# AMS_MCU.net
KiCad netlist of a schematic drawn in Altium Designer
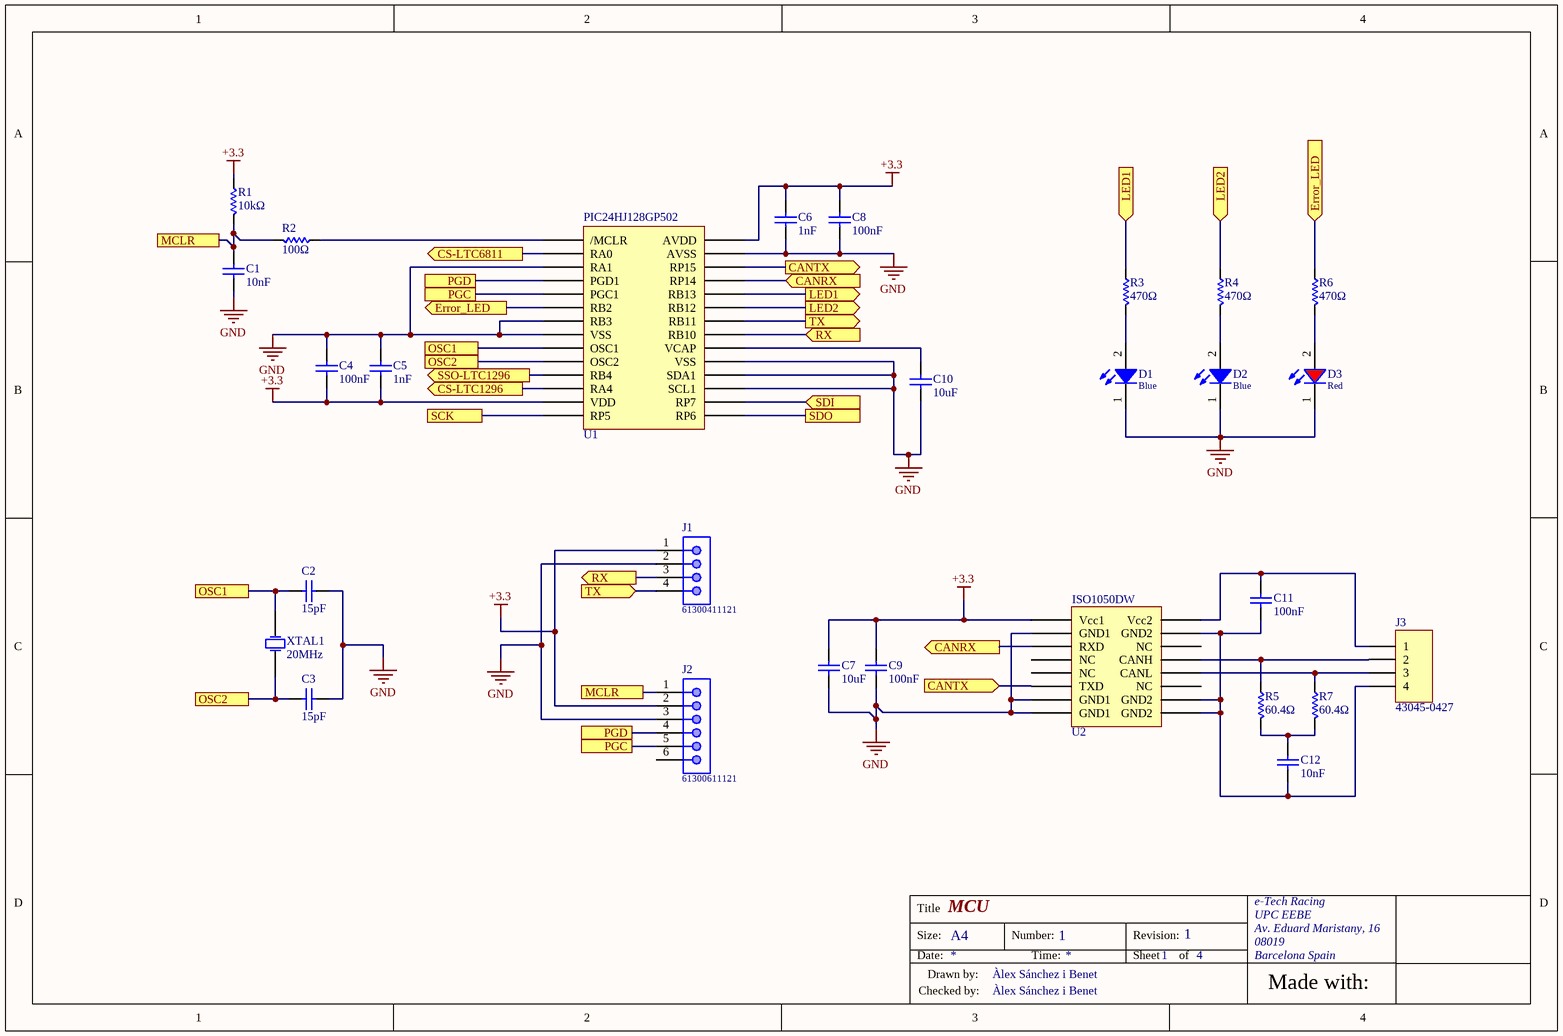
[diagram p0: AMS_MCU.SchDoc]

(export (version "E")
  (design (tool "Eeschema 10.0.6"))
  (components
    (comp (ref "C1")
      (value "10nF")
      (footprint "0805_2x1.25x0.8mm_Reflow Soldering")
      (description "WCAP-CSGP Ceramic Capacitors, 0805, X7R, 50V, 10nF")
      (fields (field (name "PART NUMBER") "885012207092") (field (name "PUBLISHER") "Wurth Elektronik"))
      (libsource (lib "Components_Library") (part "885012207092"))
    )
    (comp (ref "C2")
      (value "15pF")
      (footprint "0805_2x1.25x0.6mm_Reflow Soldering")
      (description "WCAP-CSGP Ceramic Capacitors, 0805, NP0, 50V, 15pF")
      (fields (field (name "PART NUMBER") "885012007052") (field (name "PUBLISHER") "Wurth Elektronik"))
      (libsource (lib "Components_Library") (part "885012007052"))
    )
    (comp (ref "C3")
      (value "15pF")
      (footprint "0805_2x1.25x0.6mm_Reflow Soldering")
      (description "WCAP-CSGP Ceramic Capacitors, 0805, NP0, 50V, 15pF")
      (fields (field (name "PART NUMBER") "885012007052") (field (name "PUBLISHER") "Wurth Elektronik"))
      (libsource (lib "Components_Library") (part "885012007052"))
    )
    (comp (ref "C4")
      (value "100nF")
      (footprint "0805_2x1.25x0.8mm_Reflow Soldering")
      (description "WCAP-CSGP Ceramic Capacitors, 0805, X7R, 50V, 100nF")
      (fields (field (name "PART NUMBER") "885012207098") (field (name "PUBLISHER") "Wurth Elektronik"))
      (libsource (lib "Components_Library") (part "885012207098"))
    )
    (comp (ref "C5")
      (value "1nF")
      (footprint "0805_2x1.25x0.8mm_Reflow Soldering")
      (description "WCAP-CSGP Ceramic Capacitors, 0805, NP0, 50V, 1nF")
      (fields (field (name "PART NUMBER") "885012007063") (field (name "PUBLISHER") "Wurth Elektronik"))
      (libsource (lib "Components_Library") (part "885012007063"))
    )
    (comp (ref "C6")
      (value "1nF")
      (footprint "0805_2x1.25x0.8mm_Reflow Soldering")
      (description "WCAP-CSGP Ceramic Capacitors, 0805, NP0, 50V, 1nF")
      (fields (field (name "PART NUMBER") "885012007063") (field (name "PUBLISHER") "Wurth Elektronik"))
      (libsource (lib "Components_Library") (part "885012007063"))
    )
    (comp (ref "C7")
      (value "10uF")
      (footprint "0805_2x1.25x1.25mm_Reflow Soldering")
      (description "WCAP-CSGP Ceramic Capacitors, 0805, X5R, 16V, 10uF")
      (fields (field (name "PART NUMBER") "885012107014") (field (name "PUBLISHER") "Wurth Elektronik"))
      (libsource (lib "Components_Library") (part "885012107014"))
    )
    (comp (ref "C8")
      (value "100nF")
      (footprint "0805_2x1.25x0.8mm_Reflow Soldering")
      (description "WCAP-CSGP Ceramic Capacitors, 0805, X7R, 50V, 100nF")
      (fields (field (name "PART NUMBER") "885012207098") (field (name "PUBLISHER") "Wurth Elektronik"))
      (libsource (lib "Components_Library") (part "885012207098"))
    )
    (comp (ref "C9")
      (value "100nF")
      (footprint "0805_2x1.25x0.8mm_Reflow Soldering")
      (description "WCAP-CSGP Ceramic Capacitors, 0805, X7R, 50V, 100nF")
      (fields (field (name "PART NUMBER") "885012207098") (field (name "PUBLISHER") "Wurth Elektronik"))
      (libsource (lib "Components_Library") (part "885012207098"))
    )
    (comp (ref "C10")
      (value "10uF")
      (footprint "0805_2x1.25x1.25mm_Reflow Soldering")
      (description "WCAP-CSGP Ceramic Capacitors, 0805, X5R, 16V, 10uF")
      (fields (field (name "PART NUMBER") "885012107014") (field (name "PUBLISHER") "Wurth Elektronik"))
      (libsource (lib "Components_Library") (part "885012107014"))
    )
    (comp (ref "C11")
      (value "100nF")
      (footprint "0805_2x1.25x0.8mm_Reflow Soldering")
      (description "WCAP-CSGP Ceramic Capacitors, 0805, X7R, 50V, 100nF")
      (fields (field (name "PART NUMBER") "885012207098") (field (name "PUBLISHER") "Wurth Elektronik"))
      (libsource (lib "Components_Library") (part "885012207098"))
    )
    (comp (ref "C12")
      (value "10nF")
      (footprint "0805_2x1.25x0.8mm_Reflow Soldering")
      (description "WCAP-CSGP Ceramic Capacitors, 0805, X7R, 50V, 10nF")
      (fields (field (name "PART NUMBER") "885012207092") (field (name "PUBLISHER") "Wurth Elektronik"))
      (libsource (lib "Components_Library") (part "885012207092"))
    )
    (comp (ref "D1")
      (value "Blue")
      (footprint "WL-SMCW_0805")
      (description "SMT Mono-color Chip LED Waterclear WL-SMCW, size 0805, Blue, 3.2 V, 140 deg, 145 mcd")
      (fields (field (name "PART NUMBER") "150080BS75000") (field (name "PUBLISHER") "Wurth Elektronik"))
      (libsource (lib "Components_Library") (part "150080BS75000"))
    )
    (comp (ref "D2")
      (value "Blue")
      (footprint "WL-SMCW_0805")
      (description "SMT Mono-color Chip LED Waterclear WL-SMCW, size 0805, Blue, 3.2 V, 140 deg, 145 mcd")
      (fields (field (name "PART NUMBER") "150080BS75000") (field (name "PUBLISHER") "Wurth Elektronik"))
      (libsource (lib "Components_Library") (part "150080BS75000"))
    )
    (comp (ref "D3")
      (value "Red")
      (footprint "WL-SMCW_0805")
      (description "SMT Mono-color Chip LED Waterclear WL-SMCW, size 0805, Red, 2 V, 140 deg, 150 mcd")
      (fields (field (name "PART NUMBER") "150080RS75000") (field (name "PUBLISHER") "Wurth Elektronik"))
      (libsource (lib "Components_Library") (part "150080RS75000"))
    )
    (comp (ref "J1")
      (value "61300411121")
      (footprint "61300411121")
      (description "THT Vertical Pin Header WR-PHD, Pitch 2.54 mm, Single Row, 4 pins")
      (fields (field (name "PUBLISHER") "Wurth Elektronik"))
      (libsource (lib "Components_Library") (part "61300411121"))
    )
    (comp (ref "J2")
      (value "61300611121")
      (footprint "61300611121")
      (description "THT Vertical Pin Header WR-PHD, Pitch 2.54 mm, Single Row, 6 pins")
      (fields (field (name "PUBLISHER") "Wurth Elektronik"))
      (libsource (lib "Components_Library") (part "61300611121"))
    )
    (comp (ref "J3")
      (value "43045-0427")
      (footprint "43045-0427")
      (description "Micro-Fit 3.0 Vertical Header, 3.00mm Pitch, Dual Row, 4 Circuits, Black")
      (fields (field (name "MANUFACTURER") "Molex"))
      (libsource (lib "Components_Library") (part "43045-0427"))
    )
    (comp (ref "R1")
      (value "10kΩ")
      (footprint "CR0805")
      (description "Chip Resistor 0805")
      (fields (field (name "MANUFACTURER") "Bourns"))
      (libsource (lib "Components_Library") (part "CR0805-JW-103ELF"))
    )
    (comp (ref "R2")
      (value "100Ω")
      (footprint "CR0805")
      (description "Chip Resistor 0805")
      (fields (field (name "MANUFACTURER") "Bourns"))
      (libsource (lib "Components_Library") (part "CR0805-FX-1000ELF"))
    )
    (comp (ref "R3")
      (value "470Ω")
      (footprint "CR0805")
      (description "Chip Resistor 0805")
      (fields (field (name "MANUFACTURER") "Bourns"))
      (libsource (lib "Components_Library") (part "CR0805-FX-4700GLF"))
    )
    (comp (ref "R4")
      (value "470Ω")
      (footprint "CR0805")
      (description "Chip Resistor 0805")
      (fields (field (name "MANUFACTURER") "Bourns"))
      (libsource (lib "Components_Library") (part "CR0805-FX-4700GLF"))
    )
    (comp (ref "R5")
      (value "60.4Ω")
      (footprint "CR0805")
      (description "Chip Resistor 0805")
      (fields (field (name "MANUFACTURER") "Panasonic"))
      (libsource (lib "Components_Library") (part "ERA6AEB60R4V"))
    )
    (comp (ref "R6")
      (value "470Ω")
      (footprint "CR0805")
      (description "Chip Resistor 0805")
      (fields (field (name "MANUFACTURER") "Bourns"))
      (libsource (lib "Components_Library") (part "CR0805-FX-4700GLF"))
    )
    (comp (ref "R7")
      (value "60.4Ω")
      (footprint "CR0805")
      (description "Chip Resistor 0805")
      (fields (field (name "MANUFACTURER") "Panasonic"))
      (libsource (lib "Components_Library") (part "ERA6AEB60R4V"))
    )
    (comp (ref "U1")
      (value "PIC24HJ128GP502")
      (footprint "PIC24HJ128GP502")
      (description "16-bit Microcontroller\r\n(up to 128 KB Flash and 8K SRAM) with Advanced Analog")
      (fields (field (name "MANUFACTURER") "Microchip"))
      (libsource (lib "Components_Library") (part "PIC24HJ128GP502"))
    )
    (comp (ref "U2")
      (value "ISO1050DW")
      (footprint "ISO1050DW")
      (description "Galvanically isolated CAN\r\ntransceiver")
      (fields (field (name "MANUFACTURER") "Texas Instruments"))
      (libsource (lib "Components_Library") (part "ISO1050DW"))
    )
    (comp (ref "XTAL1")
      (value "20MHz")
      (footprint "830028710")
      (description "Industry standard SMD crystal WE-XTAL Quartz Crystal")
      (fields (field (name "MANUFACTURER") "Wurth Elektronik"))
      (libsource (lib "Components_Library") (part "830028710"))
    )
  )
  (nets
    (net (code "1") (name "+3.3") (class "Default")
      (node (ref "C4") (pin "1") (pinfunction "1_1") (pintype "passive"))
      (node (ref "C5") (pin "1") (pinfunction "1_1") (pintype "passive"))
      (node (ref "C6") (pin "2") (pinfunction "2_2") (pintype "passive"))
      (node (ref "C7") (pin "2") (pinfunction "2_2") (pintype "passive"))
      (node (ref "C8") (pin "2") (pinfunction "2_2") (pintype "passive"))
      (node (ref "C9") (pin "2") (pinfunction "2_2") (pintype "passive"))
      (node (ref "J1") (pin "1") (pinfunction "1_1") (pintype "passive"))
      (node (ref "J2") (pin "2") (pinfunction "2_2") (pintype "passive"))
      (node (ref "R1") (pin "2") (pinfunction "2_2") (pintype "passive"))
      (node (ref "U1") (pin "13") (pinfunction "VDD_13") (pintype "passive"))
      (node (ref "U1") (pin "28") (pinfunction "AVDD_28") (pintype "passive"))
      (node (ref "U2") (pin "1") (pinfunction "Vcc1_1") (pintype "passive"))
    )
    (net (code "2") (name "/CANRX") (class "Default")
      (node (ref "U1") (pin "25") (pinfunction "RP14_25") (pintype "passive"))
      (node (ref "U2") (pin "3") (pinfunction "RXD_3") (pintype "passive"))
    )
    (net (code "3") (name "/CANTX") (class "Default")
      (node (ref "U1") (pin "26") (pinfunction "RP15_26") (pintype "passive"))
      (node (ref "U2") (pin "6") (pinfunction "TXD_6") (pintype "passive"))
    )
    (net (code "4") (name "/CS-LTC1296") (class "Default")
      (node (ref "U1") (pin "12") (pinfunction "RA4_12") (pintype "passive"))
    )
    (net (code "5") (name "/CS-LTC6811") (class "Default")
      (node (ref "U1") (pin "2") (pinfunction "RA0_2") (pintype "passive"))
    )
    (net (code "6") (name "/Error_LED") (class "Default")
      (node (ref "R6") (pin "2") (pinfunction "2_2") (pintype "passive"))
      (node (ref "U1") (pin "6") (pinfunction "RB2_6") (pintype "passive"))
    )
    (net (code "7") (name "/LED1") (class "Default")
      (node (ref "R3") (pin "2") (pinfunction "2_2") (pintype "passive"))
      (node (ref "U1") (pin "24") (pinfunction "RB13_24") (pintype "passive"))
    )
    (net (code "8") (name "/LED2") (class "Default")
      (node (ref "R4") (pin "2") (pinfunction "2_2") (pintype "passive"))
      (node (ref "U1") (pin "23") (pinfunction "RB12_23") (pintype "passive"))
    )
    (net (code "9") (name "/MCLR") (class "Default")
      (node (ref "C1") (pin "2") (pinfunction "2_2") (pintype "passive"))
      (node (ref "J2") (pin "1") (pinfunction "1_1") (pintype "passive"))
      (node (ref "R1") (pin "1") (pinfunction "1_1") (pintype "passive"))
      (node (ref "R2") (pin "1") (pinfunction "1_1") (pintype "passive"))
    )
    (net (code "10") (name "/OSC1") (class "Default")
      (node (ref "C2") (pin "1") (pinfunction "1_1") (pintype "passive"))
      (node (ref "U1") (pin "9") (pinfunction "OSC1_9") (pintype "passive"))
      (node (ref "XTAL1") (pin "2") (pinfunction "OSC2_2") (pintype "passive"))
    )
    (net (code "11") (name "/OSC2") (class "Default")
      (node (ref "C3") (pin "1") (pinfunction "1_1") (pintype "passive"))
      (node (ref "U1") (pin "10") (pinfunction "OSC2_10") (pintype "passive"))
      (node (ref "XTAL1") (pin "1") (pinfunction "OSC1_1") (pintype "passive"))
    )
    (net (code "12") (name "/PGC") (class "Default")
      (node (ref "J2") (pin "5") (pinfunction "5_5") (pintype "passive"))
      (node (ref "U1") (pin "5") (pinfunction "PGC1_5") (pintype "passive"))
    )
    (net (code "13") (name "/PGD") (class "Default")
      (node (ref "J2") (pin "4") (pinfunction "4_4") (pintype "passive"))
      (node (ref "U1") (pin "4") (pinfunction "PGD1_4") (pintype "passive"))
    )
    (net (code "14") (name "/RX") (class "Default")
      (node (ref "J1") (pin "3") (pinfunction "3_3") (pintype "passive"))
      (node (ref "U1") (pin "21") (pinfunction "RB10_21") (pintype "passive"))
    )
    (net (code "15") (name "/SCK") (class "Default")
      (node (ref "U1") (pin "14") (pinfunction "RP5_14") (pintype "passive"))
    )
    (net (code "16") (name "/SDI") (class "Default")
      (node (ref "U1") (pin "16") (pinfunction "RP7_16") (pintype "passive"))
    )
    (net (code "17") (name "/SDO") (class "Default")
      (node (ref "U1") (pin "15") (pinfunction "RP6_15") (pintype "passive"))
    )
    (net (code "18") (name "/SSO-LTC1296") (class "Default")
      (node (ref "U1") (pin "11") (pinfunction "RB4_11") (pintype "passive"))
    )
    (net (code "19") (name "/TX") (class "Default")
      (node (ref "J1") (pin "4") (pinfunction "4_4") (pintype "passive"))
      (node (ref "U1") (pin "22") (pinfunction "RB11_22") (pintype "passive"))
    )
    (net (code "20") (name "GND") (class "Default")
      (node (ref "C1") (pin "1") (pinfunction "1_1") (pintype "passive"))
      (node (ref "C10") (pin "1") (pinfunction "1_1") (pintype "passive"))
      (node (ref "C2") (pin "2") (pinfunction "2_2") (pintype "passive"))
      (node (ref "C3") (pin "2") (pinfunction "2_2") (pintype "passive"))
      (node (ref "C4") (pin "2") (pinfunction "2_2") (pintype "passive"))
      (node (ref "C5") (pin "2") (pinfunction "2_2") (pintype "passive"))
      (node (ref "C6") (pin "1") (pinfunction "1_1") (pintype "passive"))
      (node (ref "C7") (pin "1") (pinfunction "1_1") (pintype "passive"))
      (node (ref "C8") (pin "1") (pinfunction "1_1") (pintype "passive"))
      (node (ref "C9") (pin "1") (pinfunction "1_1") (pintype "passive"))
      (node (ref "D1") (pin "1") (pinfunction "K_1") (pintype "passive"))
      (node (ref "D2") (pin "1") (pinfunction "K_1") (pintype "passive"))
      (node (ref "D3") (pin "1") (pinfunction "K_1") (pintype "passive"))
      (node (ref "J1") (pin "2") (pinfunction "2_2") (pintype "passive"))
      (node (ref "J2") (pin "3") (pinfunction "3_3") (pintype "passive"))
      (node (ref "U1") (pin "17") (pinfunction "SCL1_17") (pintype "passive"))
      (node (ref "U1") (pin "18") (pinfunction "SDA1_18") (pintype "passive"))
      (node (ref "U1") (pin "19") (pinfunction "VSS_19") (pintype "passive"))
      (node (ref "U1") (pin "27") (pinfunction "AVSS_27") (pintype "passive"))
      (node (ref "U1") (pin "3") (pinfunction "RA1_3") (pintype "passive"))
      (node (ref "U1") (pin "7") (pinfunction "RB3_7") (pintype "passive"))
      (node (ref "U1") (pin "8") (pinfunction "VSS_8") (pintype "passive"))
      (node (ref "U2") (pin "2") (pinfunction "GND1_2") (pintype "passive"))
      (node (ref "U2") (pin "7") (pinfunction "GND1_7") (pintype "passive"))
      (node (ref "U2") (pin "8") (pinfunction "GND1_8") (pintype "passive"))
    )
    (net (code "21") (name "Net-(C11-Pad1)") (class "Default")
      (node (ref "C11") (pin "1") (pinfunction "1_1") (pintype "passive"))
      (node (ref "C12") (pin "1") (pinfunction "1_1") (pintype "passive"))
      (node (ref "J3") (pin "4") (pinfunction "4_4") (pintype "passive"))
      (node (ref "U2") (pin "10") (pinfunction "GND2_10") (pintype "passive"))
      (node (ref "U2") (pin "15") (pinfunction "GND2_15") (pintype "passive"))
      (node (ref "U2") (pin "9") (pinfunction "GND2_9") (pintype "passive"))
    )
    (net (code "22") (name "Net-(C12-Pad2)") (class "Default")
      (node (ref "C12") (pin "2") (pinfunction "2_2") (pintype "passive"))
      (node (ref "R5") (pin "1") (pinfunction "1_1") (pintype "passive"))
      (node (ref "R7") (pin "1") (pinfunction "1_1") (pintype "passive"))
    )
    (net (code "23") (name "Net-(D1-A)") (class "Default")
      (node (ref "D1") (pin "2") (pinfunction "A_2") (pintype "passive"))
      (node (ref "R3") (pin "1") (pinfunction "1_1") (pintype "passive"))
    )
    (net (code "24") (name "Net-(D2-A)") (class "Default")
      (node (ref "D2") (pin "2") (pinfunction "A_2") (pintype "passive"))
      (node (ref "R4") (pin "1") (pinfunction "1_1") (pintype "passive"))
    )
    (net (code "25") (name "Net-(D3-A)") (class "Default")
      (node (ref "D3") (pin "2") (pinfunction "A_2") (pintype "passive"))
      (node (ref "R6") (pin "1") (pinfunction "1_1") (pintype "passive"))
    )
    (net (code "26") (name "Net-(U1-VCAP)") (class "Default")
      (node (ref "C10") (pin "2") (pinfunction "2_2") (pintype "passive"))
      (node (ref "U1") (pin "20") (pinfunction "VCAP_20") (pintype "passive"))
    )
    (net (code "27") (name "Net-(U1-{slash}MCLR)") (class "Default")
      (node (ref "R2") (pin "2") (pinfunction "2_2") (pintype "passive"))
      (node (ref "U1") (pin "1") (pinfunction "/MCLR_1") (pintype "passive"))
    )
    (net (code "28") (name "Net-(U2-CANH)") (class "Default")
      (node (ref "J3") (pin "2") (pinfunction "2_2") (pintype "passive"))
      (node (ref "R5") (pin "2") (pinfunction "2_2") (pintype "passive"))
      (node (ref "U2") (pin "13") (pinfunction "CANH_13") (pintype "passive"))
    )
    (net (code "29") (name "Net-(U2-CANL)") (class "Default")
      (node (ref "J3") (pin "3") (pinfunction "3_3") (pintype "passive"))
      (node (ref "R7") (pin "2") (pinfunction "2_2") (pintype "passive"))
      (node (ref "U2") (pin "12") (pinfunction "CANL_12") (pintype "passive"))
    )
    (net (code "30") (name "Net-(U2-Vcc2)") (class "Default")
      (node (ref "C11") (pin "2") (pinfunction "2_2") (pintype "passive"))
      (node (ref "J3") (pin "1") (pinfunction "1_1") (pintype "passive"))
      (node (ref "U2") (pin "16") (pinfunction "Vcc2_16") (pintype "passive"))
    )
    (net (code "31") (name "unconnected-(J2-Pad6)") (class "Default")
      (node (ref "J2") (pin "6") (pinfunction "6_6") (pintype "passive"))
    )
    (net (code "32") (name "unconnected-(U2-NC-Pad4)") (class "Default")
      (node (ref "U2") (pin "4") (pinfunction "NC_4") (pintype "passive"))
    )
    (net (code "33") (name "unconnected-(U2-NC-Pad5)") (class "Default")
      (node (ref "U2") (pin "5") (pinfunction "NC_5") (pintype "passive"))
    )
    (net (code "34") (name "unconnected-(U2-NC-Pad11)") (class "Default")
      (node (ref "U2") (pin "11") (pinfunction "NC_11") (pintype "passive"))
    )
    (net (code "35") (name "unconnected-(U2-NC-Pad14)") (class "Default")
      (node (ref "U2") (pin "14") (pinfunction "NC_14") (pintype "passive"))
    )
  )
)
